# schematic.net
KiCad netlist of a schematic drawn in EasyEDA
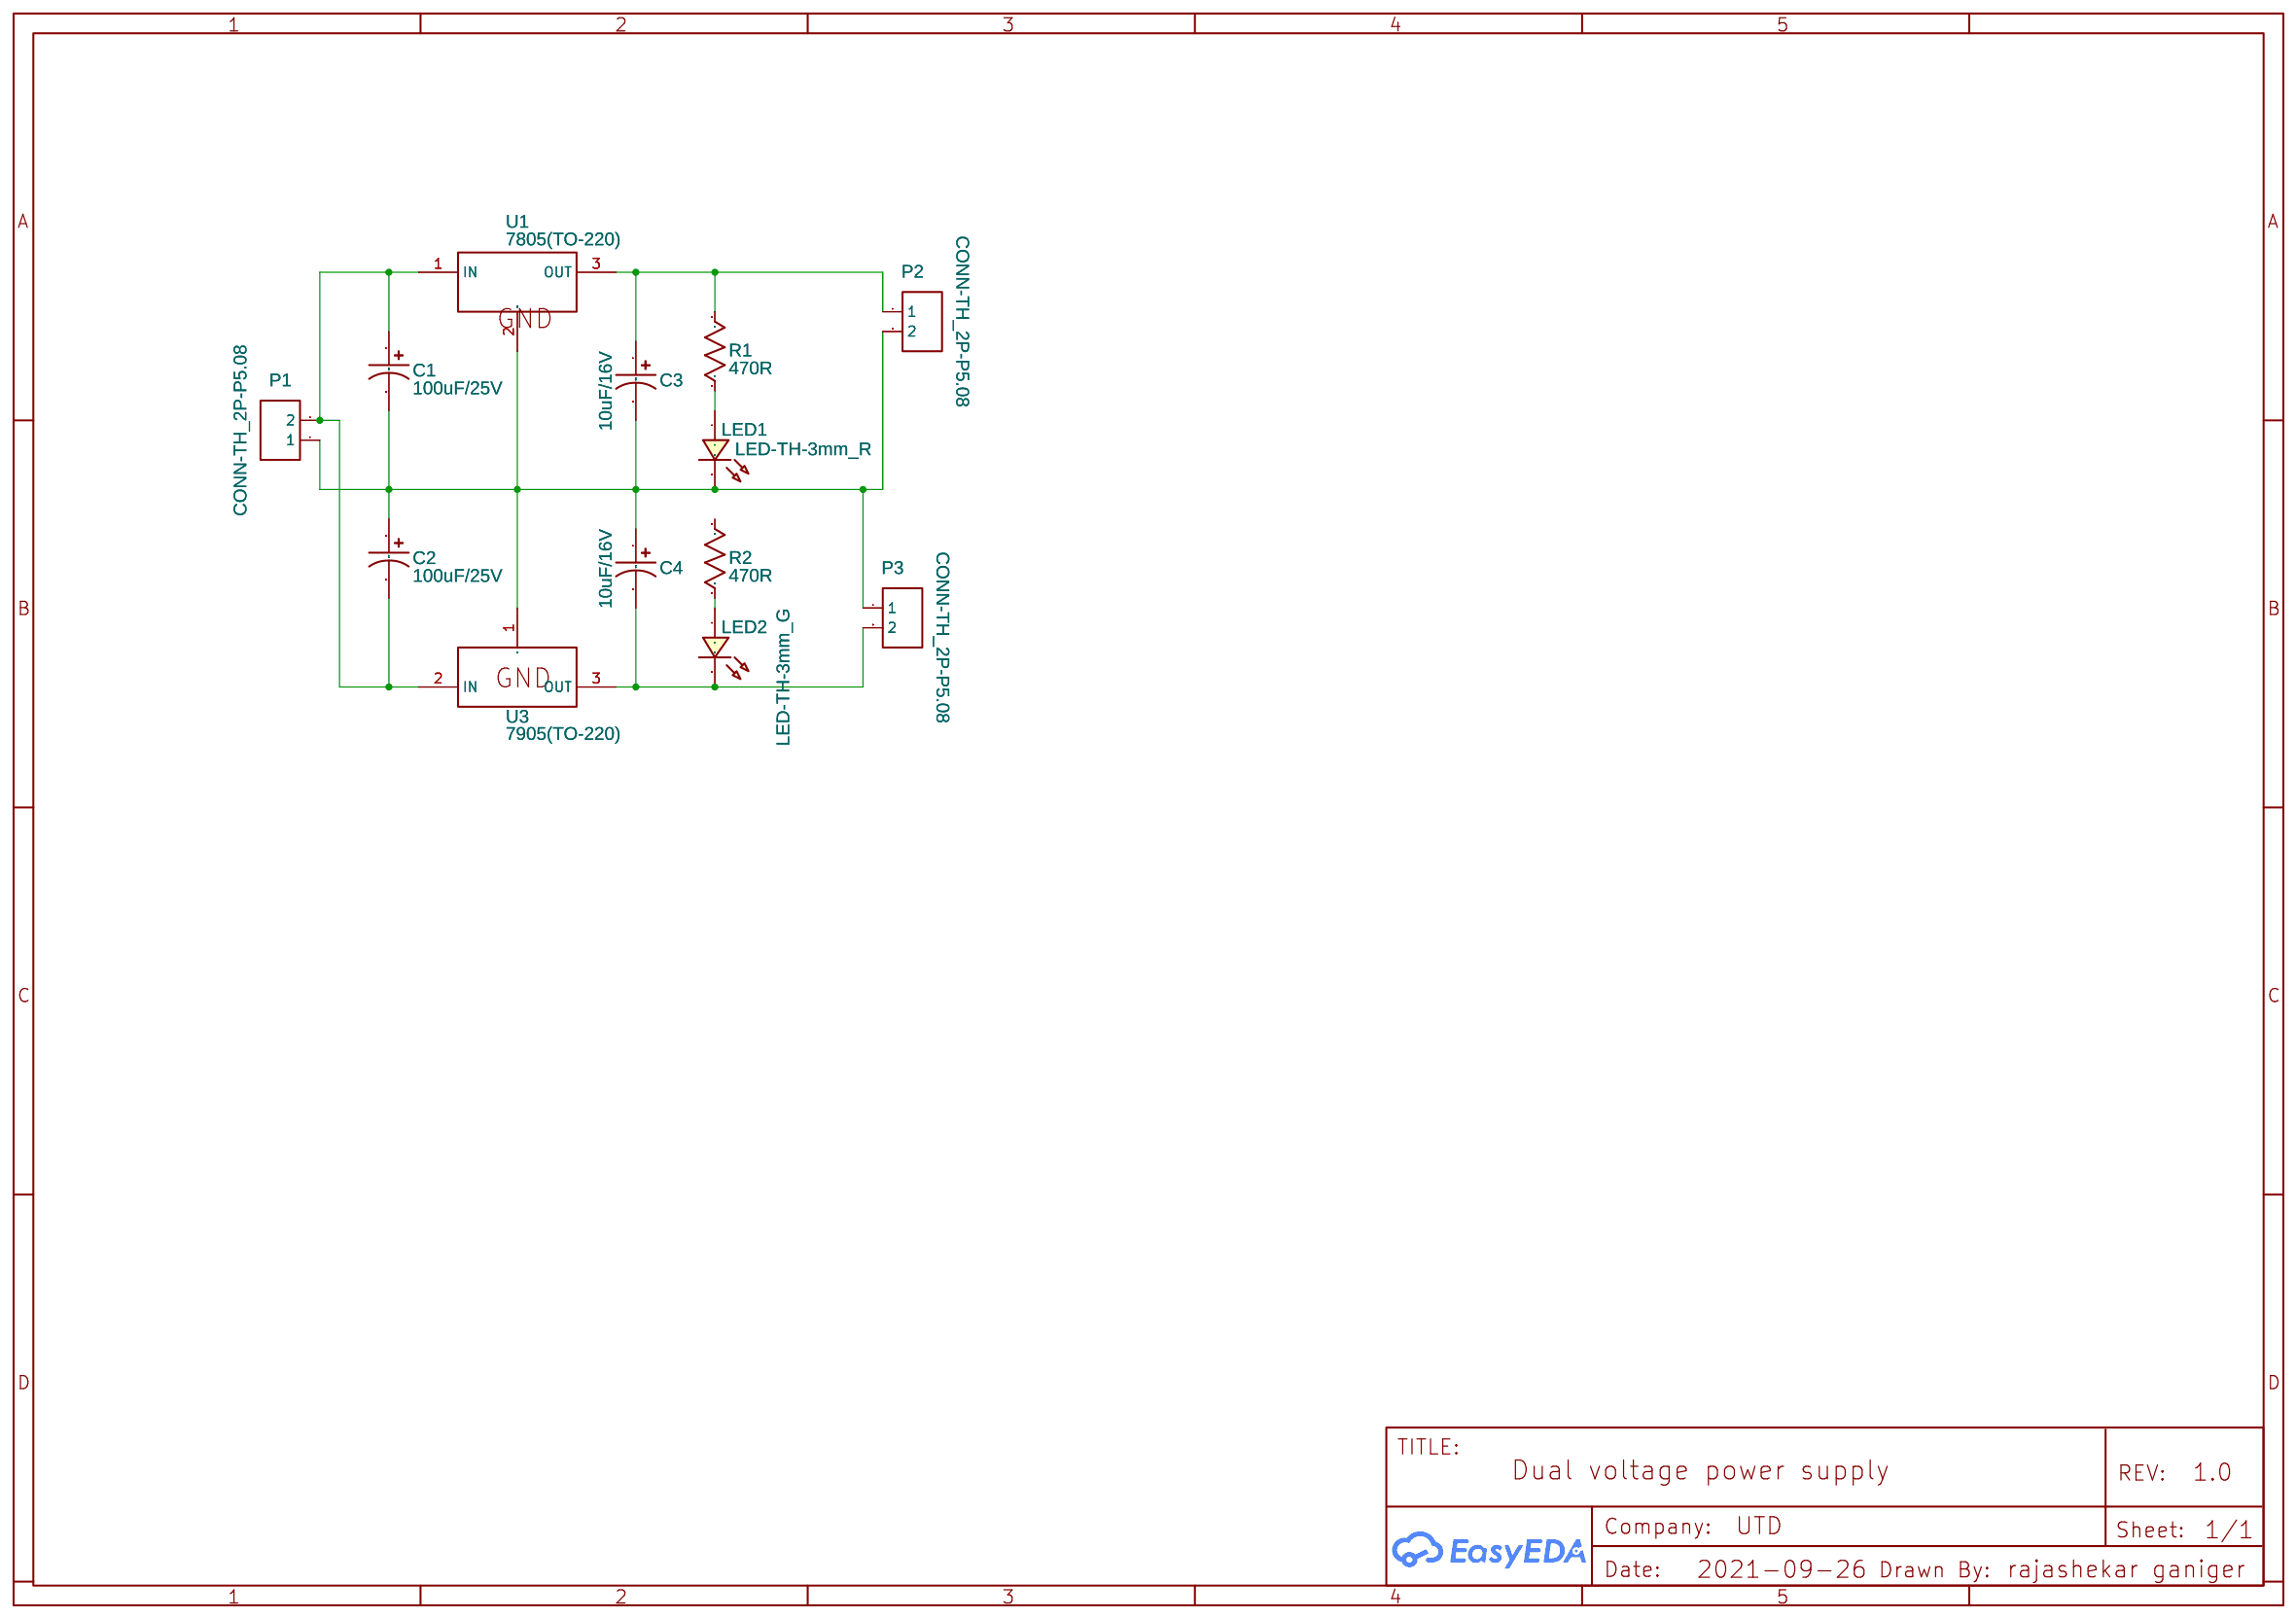
[diagram p0: schematic sheet]

(export (version "E")
  (design (tool "Eeschema 10.0.6"))
  (components
    (comp (ref "C1") (value "100uF/25V") (libsource (lib "") (part "CE_TH_D6.3×F2.5_US_1")))
    (comp (ref "C2") (value "100uF/25V") (libsource (lib "") (part "CE_TH_D6.3×F2.5_US_1")))
    (comp (ref "C3") (value "10uF/16V") (libsource (lib "") (part "CE_TH_D6.3×F2.5_US")))
    (comp (ref "C4") (value "10uF/16V") (libsource (lib "") (part "CE_TH_D6.3×F2.5_US")))
    (comp (ref "LED1")
      (value "LED-TH-3mm_R")
      (fields
        (field (name "BOM_Manufacturer Part") "204-10SDRD/S530-A3-L")
        (field (name "BOM_Supplier Part") "C84774")
      )
      (libsource (lib "") (part "LED-TH-3mm_R"))
    )
    (comp (ref "LED2")
      (value "LED-TH-3mm_G")
      (fields
        (field (name "BOM_Manufacturer Part") "204-10SYGD/S530-E3")
        (field (name "BOM_Supplier Part") "C85161")
      )
      (libsource (lib "") (part "LED-TH-3mm_G"))
    )
    (comp (ref "P1") (value "CONN-TH_2P-P5.08") (libsource (lib "") (part "CONN-TH_2P-P5.08_1")))
    (comp (ref "P2") (value "CONN-TH_2P-P5.08") (libsource (lib "") (part "CONN-TH_2P-P5.08")))
    (comp (ref "P3") (value "CONN-TH_2P-P5.08") (libsource (lib "") (part "CONN-TH_2P-P5.08")))
    (comp (ref "R1") (value "470R") (libsource (lib "") (part "R_AXIAL-0.3_US")))
    (comp (ref "R2") (value "470R") (libsource (lib "") (part "R_AXIAL-0.3_US")))
    (comp (ref "U1")
      (value "7805(TO-220)")
      (fields (field (name "BOM_Manufacturer Part") "L7805CV-DG") (field (name "BOM_Supplier Part") "C3795"))
      (libsource (lib "") (part "7805(TO-220)"))
    )
    (comp (ref "U3")
      (value "7905(TO-220)")
      (fields (field (name "BOM_Manufacturer Part") "L7905CV-DG") (field (name "BOM_Supplier Part") "C3799"))
      (libsource (lib "") (part "7905(TO-220)"))
    )
  )
  (nets
    (net (code "1") (name "Net-(LED1-Pad1)") (class "Default")
      (node (ref "LED1") (pin "1") (pinfunction "1_1") (pintype "unspecified"))
      (node (ref "R1") (pin "1") (pinfunction "1_1") (pintype "unspecified"))
    )
    (net (code "2") (name "Net-(LED2-Pad1)") (class "Default")
      (node (ref "LED2") (pin "1") (pinfunction "1_1") (pintype "unspecified"))
      (node (ref "R2") (pin "1") (pinfunction "1_1") (pintype "unspecified"))
    )
    (net (code "3") (name "Net-(U1-GND)") (class "Default")
      (node (ref "C1") (pin "2") (pinfunction "2_2") (pintype "unspecified"))
      (node (ref "C2") (pin "1") (pinfunction "1_1") (pintype "unspecified"))
      (node (ref "C3") (pin "2") (pinfunction "2_2") (pintype "unspecified"))
      (node (ref "C4") (pin "1") (pinfunction "1_1") (pintype "unspecified"))
      (node (ref "LED1") (pin "2") (pinfunction "2_2") (pintype "unspecified"))
      (node (ref "P1") (pin "1") (pinfunction "1_1") (pintype "unspecified"))
      (node (ref "P2") (pin "2") (pinfunction "2_2") (pintype "unspecified"))
      (node (ref "P3") (pin "1") (pinfunction "1_1") (pintype "unspecified"))
      (node (ref "U1") (pin "2") (pinfunction "GND_2") (pintype "passive"))
      (node (ref "U3") (pin "1") (pinfunction "GND_1") (pintype "passive"))
    )
    (net (code "4") (name "Net-(U1-IN)") (class "Default")
      (node (ref "C1") (pin "1") (pinfunction "1_1") (pintype "unspecified"))
      (node (ref "C2") (pin "2") (pinfunction "2_2") (pintype "unspecified"))
      (node (ref "P1") (pin "2") (pinfunction "2_2") (pintype "unspecified"))
      (node (ref "U1") (pin "1") (pinfunction "IN_1") (pintype "passive"))
      (node (ref "U3") (pin "2") (pinfunction "IN_2") (pintype "passive"))
    )
    (net (code "5") (name "Net-(U1-OUT)") (class "Default")
      (node (ref "C3") (pin "1") (pinfunction "1_1") (pintype "unspecified"))
      (node (ref "P2") (pin "1") (pinfunction "1_1") (pintype "unspecified"))
      (node (ref "R1") (pin "2") (pinfunction "2_2") (pintype "unspecified"))
      (node (ref "U1") (pin "3") (pinfunction "OUT_3") (pintype "passive"))
    )
    (net (code "6") (name "Net-(U3-OUT)") (class "Default")
      (node (ref "C4") (pin "2") (pinfunction "2_2") (pintype "unspecified"))
      (node (ref "LED2") (pin "2") (pinfunction "2_2") (pintype "unspecified"))
      (node (ref "P3") (pin "2") (pinfunction "2_2") (pintype "unspecified"))
      (node (ref "U3") (pin "3") (pinfunction "OUT_3") (pintype "passive"))
    )
    (net (code "7") (name "unconnected-(R2-Pad2)") (class "Default")
      (node (ref "R2") (pin "2") (pinfunction "2_2") (pintype "unspecified"))
    )
  )
)
